# OpAmpDiffHS2.net
KiCad netlist of a schematic drawn in Altium Designer
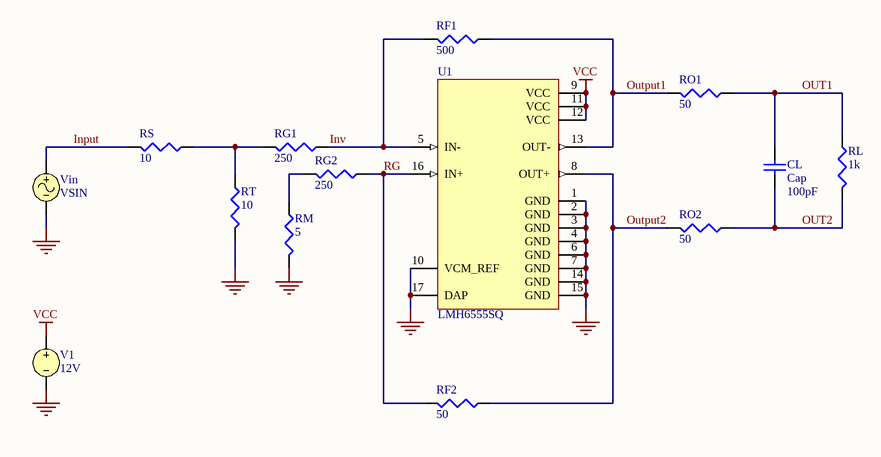
[diagram p0: OpAmpDiffHS2.schdoc]

(export (version "E")
  (design (tool "Eeschema 10.0.6"))
  (components
    (comp (ref "CL")
      (value "Cap")
      (footprint "RAD-0.3")
      (description "Capacitor")
      (fields (field (name "ALTIUM_VALUE") "100pF") (field (name "PUBLISHER") "Altium Limited"))
      (libsource (lib "Miscellaneous Devices") (part "Cap"))
    )
    (comp (ref "RF1")
      (value "500")
      (description "Resistor")
      (fields (field (name "Comment") "100k"))
      (libsource (lib "*") (part "RES"))
    )
    (comp (ref "RF2")
      (value "50")
      (description "Resistor")
      (fields (field (name "Comment") "100k"))
      (libsource (lib "*") (part "RES"))
    )
    (comp (ref "RG1")
      (value "250")
      (description "Resistor")
      (fields (field (name "Comment") "10k"))
      (libsource (lib "*") (part "RES"))
    )
    (comp (ref "RG2")
      (value "250")
      (description "Resistor")
      (fields (field (name "Comment") "10k"))
      (libsource (lib "*") (part "RES"))
    )
    (comp (ref "RL")
      (value "1k")
      (description "Resistor")
      (fields (field (name "Comment") "25k"))
      (libsource (lib "") (part "RES_1"))
    )
    (comp (ref "RM")
      (value "5")
      (description "Resistor")
      (fields (field (name "Comment") "10k"))
      (libsource (lib "") (part "RES_1"))
    )
    (comp (ref "RO1")
      (value "50")
      (description "Resistor")
      (fields (field (name "Comment") "25k"))
      (libsource (lib "*") (part "RES"))
    )
    (comp (ref "RO2")
      (value "50")
      (description "Resistor")
      (fields (field (name "Comment") "25k"))
      (libsource (lib "*") (part "RES"))
    )
    (comp (ref "RS")
      (value "10")
      (description "Resistor")
      (fields (field (name "Comment") "10k"))
      (libsource (lib "*") (part "RES"))
    )
    (comp (ref "RT")
      (value "10")
      (description "Resistor")
      (fields (field (name "Comment") "10k"))
      (libsource (lib "") (part "RES_1"))
    )
    (comp (ref "U1")
      (value "LMH6555SQ")
      (footprint "SQA16A")
      (description "Low Distortion 1.2 GHz Differential Driver")
      (fields
        (field (name "MANUFACTURER") "National Semiconductor")
        (field (name "DIGIKEYPARTNUMBER") "LMH6555SQCT-ND")
        (field (name "PUBLISHER") "Altium Limited")
      )
      (libsource (lib "NSC Amplifier with SIM models") (part "LMH6555SQ"))
    )
    (comp (ref "V1") (value "12V") (description "Voltage Source") (libsource (lib "*") (part "VSRC")))
    (comp (ref "Vin")
      (value "VSIN")
      (description "Sinusoidal Voltage Source")
      (libsource (lib "*") (part "VSIN"))
    )
  )
  (nets
    (net (code "1") (name "/Input") (class "Default")
      (node (ref "RS") (pin "1") (pinfunction "TOP_1") (pintype "passive"))
      (node (ref "Vin") (pin "1") (pinfunction "1_1") (pintype "passive"))
    )
    (net (code "2") (name "/Inv") (class "Default")
      (node (ref "RF1") (pin "1") (pinfunction "TOP_1") (pintype "passive"))
      (node (ref "RG1") (pin "2") (pinfunction "BOT_2") (pintype "passive"))
      (node (ref "U1") (pin "5") (pinfunction "IN-_5") (pintype "input"))
    )
    (net (code "3") (name "/OUT1") (class "Default")
      (node (ref "CL") (pin "2") (pinfunction "2_2") (pintype "passive"))
      (node (ref "RL") (pin "2") (pinfunction "BOT_2") (pintype "passive"))
      (node (ref "RO1") (pin "2") (pinfunction "BOT_2") (pintype "passive"))
    )
    (net (code "4") (name "/OUT2") (class "Default")
      (node (ref "CL") (pin "1") (pinfunction "1_1") (pintype "passive"))
      (node (ref "RL") (pin "1") (pinfunction "TOP_1") (pintype "passive"))
      (node (ref "RO2") (pin "2") (pinfunction "BOT_2") (pintype "passive"))
    )
    (net (code "5") (name "/Output1") (class "Default")
      (node (ref "RF1") (pin "2") (pinfunction "BOT_2") (pintype "passive"))
      (node (ref "RO1") (pin "1") (pinfunction "TOP_1") (pintype "passive"))
      (node (ref "U1") (pin "13") (pinfunction "OUT-_13") (pintype "output"))
    )
    (net (code "6") (name "/Output2") (class "Default")
      (node (ref "RF2") (pin "2") (pinfunction "BOT_2") (pintype "passive"))
      (node (ref "RO2") (pin "1") (pinfunction "TOP_1") (pintype "passive"))
      (node (ref "U1") (pin "8") (pinfunction "OUT+_8") (pintype "output"))
    )
    (net (code "7") (name "/RG") (class "Default")
      (node (ref "RF2") (pin "1") (pinfunction "TOP_1") (pintype "passive"))
      (node (ref "RG2") (pin "2") (pinfunction "BOT_2") (pintype "passive"))
      (node (ref "U1") (pin "16") (pinfunction "IN+_16") (pintype "input"))
    )
    (net (code "8") (name "GND") (class "Default")
      (node (ref "RM") (pin "1") (pinfunction "TOP_1") (pintype "passive"))
      (node (ref "RT") (pin "1") (pinfunction "TOP_1") (pintype "passive"))
      (node (ref "U1") (pin "1") (pinfunction "GND_1") (pintype "power_in"))
      (node (ref "U1") (pin "10") (pinfunction "VCM_REF_10") (pintype "passive"))
      (node (ref "U1") (pin "14") (pinfunction "GND_14") (pintype "power_in"))
      (node (ref "U1") (pin "15") (pinfunction "GND_15") (pintype "power_in"))
      (node (ref "U1") (pin "17") (pinfunction "DAP_17") (pintype "passive"))
      (node (ref "U1") (pin "2") (pinfunction "GND_2") (pintype "power_in"))
      (node (ref "U1") (pin "3") (pinfunction "GND_3") (pintype "power_in"))
      (node (ref "U1") (pin "4") (pinfunction "GND_4") (pintype "power_in"))
      (node (ref "U1") (pin "6") (pinfunction "GND_6") (pintype "power_in"))
      (node (ref "U1") (pin "7") (pinfunction "GND_7") (pintype "power_in"))
      (node (ref "V1") (pin "2") (pinfunction "2_2") (pintype "passive"))
      (node (ref "Vin") (pin "2") (pinfunction "2_2") (pintype "passive"))
    )
    (net (code "9") (name "Net-(RG1-TOP)") (class "Default")
      (node (ref "RG1") (pin "1") (pinfunction "TOP_1") (pintype "passive"))
      (node (ref "RS") (pin "2") (pinfunction "BOT_2") (pintype "passive"))
      (node (ref "RT") (pin "2") (pinfunction "BOT_2") (pintype "passive"))
    )
    (net (code "10") (name "Net-(RG2-TOP)") (class "Default")
      (node (ref "RG2") (pin "1") (pinfunction "TOP_1") (pintype "passive"))
      (node (ref "RM") (pin "2") (pinfunction "BOT_2") (pintype "passive"))
    )
    (net (code "11") (name "VCC") (class "Default")
      (node (ref "U1") (pin "11") (pinfunction "VCC_11") (pintype "power_in"))
      (node (ref "U1") (pin "12") (pinfunction "VCC_12") (pintype "power_in"))
      (node (ref "U1") (pin "9") (pinfunction "VCC_9") (pintype "power_in"))
      (node (ref "V1") (pin "1") (pinfunction "1_1") (pintype "passive"))
    )
  )
)
